# Adafruit_I2S_Audio_UDA1334_Bonnet.net
KiCad netlist of a schematic drawn in EAGLE
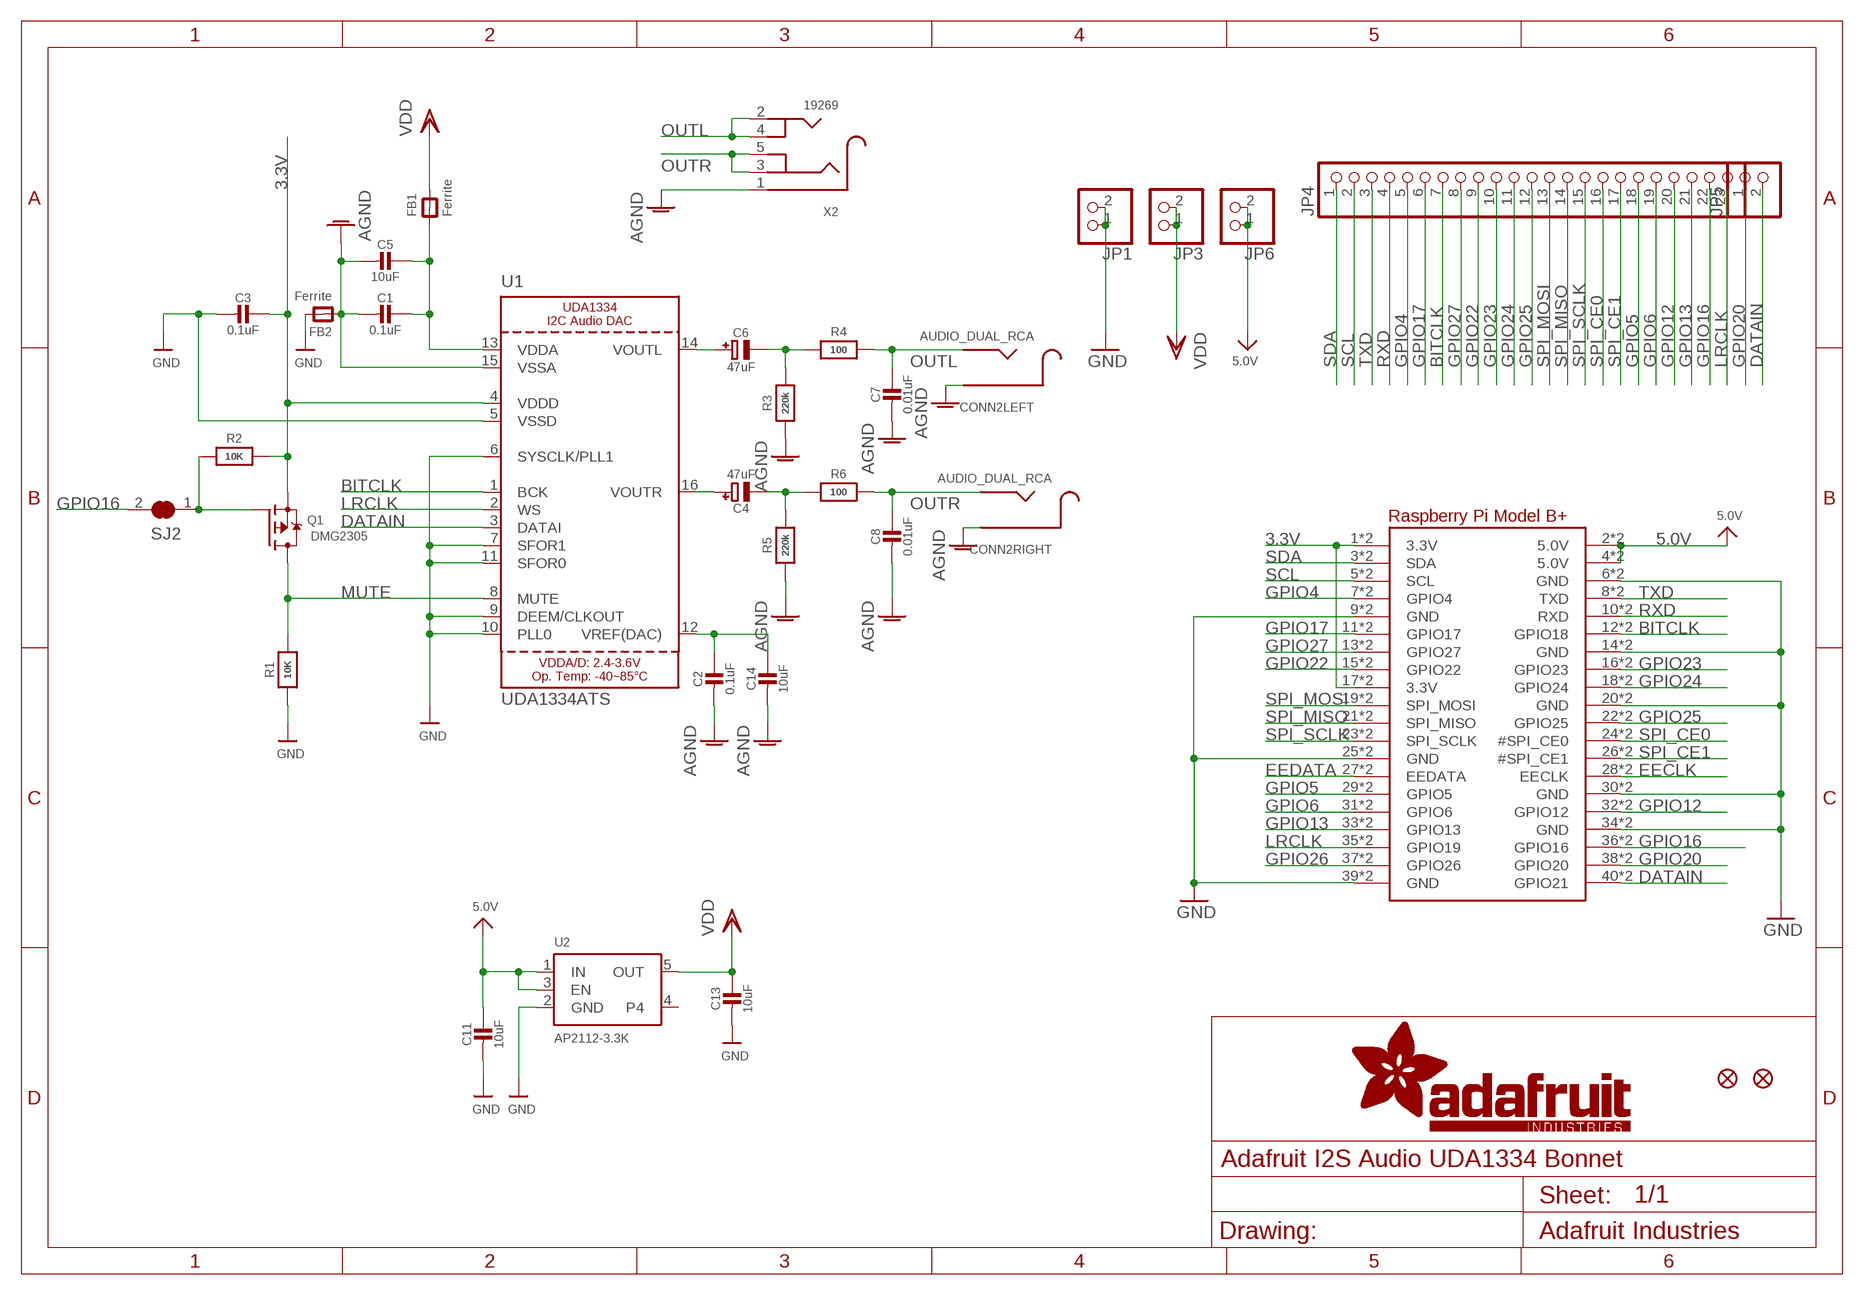
[diagram p0: schematic, sheet 1]

(export (version "E")
  (design (tool "Eeschema 10.0.6"))
  (components
    (comp (ref "C1")
      (value "0.1uF")
      (footprint "eagle-import:0603-NO")
      (libsource (lib "eagle-import") (part "CAP_CERAMIC0603_NO"))
    )
    (comp (ref "C2")
      (value "0.1uF")
      (footprint "eagle-import:0603-NO")
      (libsource (lib "eagle-import") (part "CAP_CERAMIC0603_NO"))
    )
    (comp (ref "C3")
      (value "0.1uF")
      (footprint "eagle-import:0603-NO")
      (libsource (lib "eagle-import") (part "CAP_CERAMIC0603_NO"))
    )
    (comp (ref "C4")
      (value "47uF")
      (footprint "eagle-import:PANASONIC_C")
      (libsource (lib "eagle-import") (part "CAP_ELECTROLYTICPANASONIC_C"))
    )
    (comp (ref "C5")
      (value "10uF")
      (footprint "eagle-import:0805-NO")
      (libsource (lib "eagle-import") (part "CAP_CERAMIC0805-NOOUTLINE"))
    )
    (comp (ref "C6")
      (value "47uF")
      (footprint "eagle-import:PANASONIC_C")
      (libsource (lib "eagle-import") (part "CAP_ELECTROLYTICPANASONIC_C"))
    )
    (comp (ref "C7")
      (value "0.01uF")
      (footprint "eagle-import:0603-NO")
      (libsource (lib "eagle-import") (part "CAP_CERAMIC0603_NO"))
    )
    (comp (ref "C8")
      (value "0.01uF")
      (footprint "eagle-import:0603-NO")
      (libsource (lib "eagle-import") (part "CAP_CERAMIC0603_NO"))
    )
    (comp (ref "C11")
      (value "10uF")
      (footprint "eagle-import:0805-NO")
      (libsource (lib "eagle-import") (part "CAP_CERAMIC0805-NOOUTLINE"))
    )
    (comp (ref "C13")
      (value "10uF")
      (footprint "eagle-import:0805-NO")
      (libsource (lib "eagle-import") (part "CAP_CERAMIC0805-NOOUTLINE"))
    )
    (comp (ref "C14")
      (value "10uF")
      (footprint "eagle-import:0805-NO")
      (libsource (lib "eagle-import") (part "CAP_CERAMIC0805-NOOUTLINE"))
    )
    (comp (ref "CONN2")
      (value "AUDIO_DUAL_RCA")
      (footprint "eagle-import:RCA_DUAL_JACK")
      (libsource (lib "eagle-import") (part "AUDIO_DUAL_RCA"))
    )
    (comp (ref "FB1")
      (value "Ferrite")
      (footprint "eagle-import:0805")
      (libsource (lib "eagle-import") (part "FERRITE0805"))
    )
    (comp (ref "FB2")
      (value "Ferrite")
      (footprint "eagle-import:0805")
      (libsource (lib "eagle-import") (part "FERRITE0805"))
    )
    (comp (ref "FID1")
      (value "FIDUCIAL_1MM")
      (footprint "eagle-import:FIDUCIAL_1MM")
      (libsource (lib "eagle-import") (part "FIDUCIAL_1MM"))
    )
    (comp (ref "FID2")
      (value "FIDUCIAL_1MM")
      (footprint "eagle-import:FIDUCIAL_1MM")
      (libsource (lib "eagle-import") (part "FIDUCIAL_1MM"))
    )
    (comp (ref "JP1")
      (value "HEADER-1X2ROUND")
      (footprint "eagle-import:1X02_ROUND")
      (libsource (lib "eagle-import") (part "HEADER-1X2ROUND"))
    )
    (comp (ref "JP3")
      (value "HEADER-1X2ROUND")
      (footprint "eagle-import:1X02_ROUND")
      (libsource (lib "eagle-import") (part "HEADER-1X2ROUND"))
    )
    (comp (ref "JP4")
      (value "HEADER-1X23")
      (footprint "eagle-import:1X23_ROUND_70MIL")
      (libsource (lib "eagle-import") (part "HEADER-1X23"))
    )
    (comp (ref "JP5")
      (value "HEADER-1X2ROUND")
      (footprint "eagle-import:1X02_ROUND")
      (libsource (lib "eagle-import") (part "HEADER-1X2ROUND"))
    )
    (comp (ref "JP6")
      (value "HEADER-1X2ROUND")
      (footprint "eagle-import:1X02_ROUND")
      (libsource (lib "eagle-import") (part "HEADER-1X2ROUND"))
    )
    (comp (ref "Q1")
      (value "DMG2305")
      (footprint "eagle-import:SOT23-WIDE")
      (libsource (lib "eagle-import") (part "MOSFET-PWIDE"))
    )
    (comp (ref "R1")
      (value "10K")
      (footprint "eagle-import:0603-NO")
      (libsource (lib "eagle-import") (part "RESISTOR_0603_NOOUT"))
    )
    (comp (ref "R2")
      (value "10K")
      (footprint "eagle-import:0603-NO")
      (libsource (lib "eagle-import") (part "RESISTOR_0603_NOOUT"))
    )
    (comp (ref "R3")
      (value "220k")
      (footprint "eagle-import:0603-NO")
      (libsource (lib "eagle-import") (part "RESISTOR_0603_NOOUT"))
    )
    (comp (ref "R4")
      (value "100")
      (footprint "eagle-import:0603-NO")
      (libsource (lib "eagle-import") (part "RESISTOR_0603_NOOUT"))
    )
    (comp (ref "R5")
      (value "220k")
      (footprint "eagle-import:0603-NO")
      (libsource (lib "eagle-import") (part "RESISTOR_0603_NOOUT"))
    )
    (comp (ref "R6")
      (value "100")
      (footprint "eagle-import:0603-NO")
      (libsource (lib "eagle-import") (part "RESISTOR_0603_NOOUT"))
    )
    (comp (ref "RPI1")
      (value "RASPBERRYPI_BPLUS_BONNET_THMSMT")
      (footprint "eagle-import:PI_BONNET_THMSMT")
      (libsource (lib "eagle-import") (part "RASPBERRYPI_BPLUS_BONNET_THMSMT"))
    )
    (comp (ref "SJ2")
      (value "SOLDERJUMPER_CLOSED")
      (footprint "eagle-import:SOLDERJUMPER_CLOSEDWIRE")
      (libsource (lib "eagle-import") (part "SOLDERJUMPER_CLOSED"))
    )
    (comp (ref "U1")
      (value "UDA1334ATS")
      (footprint "eagle-import:SSOP16_4.4MM")
      (libsource (lib "eagle-import") (part "AUDIO_I2S_UDA1334{dblquote}{dblquote}"))
    )
    (comp (ref "U2")
      (value "AP2112-3.3K")
      (footprint "eagle-import:SOT23-5")
      (libsource (lib "eagle-import") (part "VREG_SOT23-5"))
    )
    (comp (ref "X2")
      (value "19269")
      (footprint "eagle-import:4UCONN_19269")
      (libsource (lib "eagle-import") (part "AUDIO_3.5MMJACK"))
    )
  )
  (nets
    (net (code "1") (name "/3.3V") (class "Default")
      (node (ref "C3") (pin "1") (pinfunction "1_1") (pintype "passive"))
      (node (ref "Q1") (pin "2") (pinfunction "S_2") (pintype "passive"))
      (node (ref "R2") (pin "2") (pinfunction "2_2") (pintype "passive"))
      (node (ref "RPI1") (pin "1") (pinfunction "3.3V_1") (pintype "power_in"))
      (node (ref "RPI1") (pin "17") (pinfunction "3.3V_17") (pintype "power_in"))
      (node (ref "RPI1") (pin "S1") (pinfunction "3.3V_S1") (pintype "power_in"))
      (node (ref "RPI1") (pin "S17") (pinfunction "3.3V_S17") (pintype "power_in"))
      (node (ref "U1") (pin "4") (pinfunction "VDDD_4") (pintype "power_in"))
    )
    (net (code "2") (name "/BITCLK") (class "Default")
      (node (ref "JP4") (pin "7") (pinfunction "7_7") (pintype "passive"))
      (node (ref "RPI1") (pin "12") (pinfunction "GPIO18_12") (pintype "bidirectional"))
      (node (ref "RPI1") (pin "S12") (pinfunction "GPIO18_S12") (pintype "bidirectional"))
      (node (ref "U1") (pin "1") (pinfunction "BCK_1") (pintype "input"))
    )
    (net (code "3") (name "/DATAIN") (class "Default")
      (node (ref "JP5") (pin "2") (pinfunction "2_2") (pintype "passive"))
      (node (ref "RPI1") (pin "40") (pinfunction "GPIO21_40") (pintype "bidirectional"))
      (node (ref "RPI1") (pin "S40") (pinfunction "GPIO21_S40") (pintype "bidirectional"))
      (node (ref "U1") (pin "3") (pinfunction "DATAI_3") (pintype "input"))
    )
    (net (code "4") (name "/EECLK") (class "Default")
      (node (ref "RPI1") (pin "28") (pinfunction "EECLK_28") (pintype "bidirectional"))
      (node (ref "RPI1") (pin "S28") (pinfunction "EECLK_S28") (pintype "bidirectional"))
    )
    (net (code "5") (name "/EEDATA") (class "Default")
      (node (ref "RPI1") (pin "27") (pinfunction "EEDATA_27") (pintype "bidirectional"))
      (node (ref "RPI1") (pin "S27") (pinfunction "EEDATA_S27") (pintype "bidirectional"))
    )
    (net (code "6") (name "/GPIO4") (class "Default")
      (node (ref "JP4") (pin "5") (pinfunction "5_5") (pintype "passive"))
      (node (ref "RPI1") (pin "7") (pinfunction "GPIO4_7") (pintype "bidirectional"))
      (node (ref "RPI1") (pin "S7") (pinfunction "GPIO4_S7") (pintype "bidirectional"))
    )
    (net (code "7") (name "/GPIO5") (class "Default")
      (node (ref "JP4") (pin "18") (pinfunction "18_18") (pintype "passive"))
      (node (ref "RPI1") (pin "29") (pinfunction "GPIO5_29") (pintype "bidirectional"))
      (node (ref "RPI1") (pin "S29") (pinfunction "GPIO5_S29") (pintype "bidirectional"))
    )
    (net (code "8") (name "/GPIO6") (class "Default")
      (node (ref "JP4") (pin "19") (pinfunction "19_19") (pintype "passive"))
      (node (ref "RPI1") (pin "31") (pinfunction "GPIO6_31") (pintype "bidirectional"))
      (node (ref "RPI1") (pin "S31") (pinfunction "GPIO6_S31") (pintype "bidirectional"))
    )
    (net (code "9") (name "/GPIO12") (class "Default")
      (node (ref "JP4") (pin "20") (pinfunction "20_20") (pintype "passive"))
      (node (ref "RPI1") (pin "32") (pinfunction "GPIO12_32") (pintype "bidirectional"))
      (node (ref "RPI1") (pin "S32") (pinfunction "GPIO12_S32") (pintype "bidirectional"))
    )
    (net (code "10") (name "/GPIO13") (class "Default")
      (node (ref "JP4") (pin "21") (pinfunction "21_21") (pintype "passive"))
      (node (ref "RPI1") (pin "33") (pinfunction "GPIO13_33") (pintype "bidirectional"))
      (node (ref "RPI1") (pin "S33") (pinfunction "GPIO13_S33") (pintype "bidirectional"))
    )
    (net (code "11") (name "/GPIO16") (class "Default")
      (node (ref "JP4") (pin "22") (pinfunction "22_22") (pintype "passive"))
      (node (ref "RPI1") (pin "36") (pinfunction "GPIO16_36") (pintype "bidirectional"))
      (node (ref "RPI1") (pin "S36") (pinfunction "GPIO16_S36") (pintype "bidirectional"))
      (node (ref "SJ2") (pin "2") (pinfunction "2_2") (pintype "passive"))
    )
    (net (code "12") (name "/GPIO17") (class "Default")
      (node (ref "JP4") (pin "6") (pinfunction "6_6") (pintype "passive"))
      (node (ref "RPI1") (pin "11") (pinfunction "GPIO17_11") (pintype "bidirectional"))
      (node (ref "RPI1") (pin "S11") (pinfunction "GPIO17_S11") (pintype "bidirectional"))
    )
    (net (code "13") (name "/GPIO20") (class "Default")
      (node (ref "JP5") (pin "1") (pinfunction "1_1") (pintype "passive"))
      (node (ref "RPI1") (pin "38") (pinfunction "GPIO20_38") (pintype "bidirectional"))
      (node (ref "RPI1") (pin "S38") (pinfunction "GPIO20_S38") (pintype "bidirectional"))
    )
    (net (code "14") (name "/GPIO22") (class "Default")
      (node (ref "JP4") (pin "9") (pinfunction "9_9") (pintype "passive"))
      (node (ref "RPI1") (pin "15") (pinfunction "GPIO22_15") (pintype "bidirectional"))
      (node (ref "RPI1") (pin "S15") (pinfunction "GPIO22_S15") (pintype "bidirectional"))
    )
    (net (code "15") (name "/GPIO23") (class "Default")
      (node (ref "JP4") (pin "10") (pinfunction "10_10") (pintype "passive"))
      (node (ref "RPI1") (pin "16") (pinfunction "GPIO23_16") (pintype "bidirectional"))
      (node (ref "RPI1") (pin "S16") (pinfunction "GPIO23_S16") (pintype "bidirectional"))
    )
    (net (code "16") (name "/GPIO24") (class "Default")
      (node (ref "JP4") (pin "11") (pinfunction "11_11") (pintype "passive"))
      (node (ref "RPI1") (pin "18") (pinfunction "GPIO24_18") (pintype "bidirectional"))
      (node (ref "RPI1") (pin "S18") (pinfunction "GPIO24_S18") (pintype "bidirectional"))
    )
    (net (code "17") (name "/GPIO25") (class "Default")
      (node (ref "JP4") (pin "12") (pinfunction "12_12") (pintype "passive"))
      (node (ref "RPI1") (pin "22") (pinfunction "GPIO25_22") (pintype "bidirectional"))
      (node (ref "RPI1") (pin "S22") (pinfunction "GPIO25_S22") (pintype "bidirectional"))
    )
    (net (code "18") (name "/GPIO26") (class "Default")
      (node (ref "RPI1") (pin "37") (pinfunction "GPIO26_37") (pintype "bidirectional"))
      (node (ref "RPI1") (pin "S37") (pinfunction "GPIO26_S37") (pintype "bidirectional"))
    )
    (net (code "19") (name "/GPIO27") (class "Default")
      (node (ref "JP4") (pin "8") (pinfunction "8_8") (pintype "passive"))
      (node (ref "RPI1") (pin "13") (pinfunction "GPIO27_13") (pintype "bidirectional"))
      (node (ref "RPI1") (pin "S13") (pinfunction "GPIO27_S13") (pintype "bidirectional"))
    )
    (net (code "20") (name "/LRCLK") (class "Default")
      (node (ref "JP4") (pin "23") (pinfunction "23_23") (pintype "passive"))
      (node (ref "RPI1") (pin "35") (pinfunction "GPIO19_35") (pintype "bidirectional"))
      (node (ref "RPI1") (pin "S35") (pinfunction "GPIO19_S35") (pintype "bidirectional"))
      (node (ref "U1") (pin "2") (pinfunction "WS_2") (pintype "input"))
    )
    (net (code "21") (name "/MUTE") (class "Default")
      (node (ref "Q1") (pin "3") (pinfunction "D_3") (pintype "passive"))
      (node (ref "R1") (pin "2") (pinfunction "2_2") (pintype "passive"))
      (node (ref "U1") (pin "8") (pinfunction "MUTE_8") (pintype "input"))
    )
    (net (code "22") (name "/OUTL") (class "Default")
      (node (ref "C7") (pin "1") (pinfunction "1_1") (pintype "passive"))
      (node (ref "CONN2") (pin "L_SIG") (pinfunction "TIP_L_SIG") (pintype "bidirectional"))
      (node (ref "CONN2") (pin "L_SIG'") (pinfunction "TIP_L_SIG'") (pintype "bidirectional"))
      (node (ref "R4") (pin "2") (pinfunction "2_2") (pintype "passive"))
      (node (ref "X2") (pin "2") (pinfunction "P$5_2") (pintype "bidirectional"))
      (node (ref "X2") (pin "4") (pinfunction "P$4_4") (pintype "bidirectional"))
    )
    (net (code "23") (name "/OUTR") (class "Default")
      (node (ref "C8") (pin "1") (pinfunction "1_1") (pintype "passive"))
      (node (ref "CONN2") (pin "R_SIG") (pinfunction "TIP_R_SIG") (pintype "bidirectional"))
      (node (ref "CONN2") (pin "R_SIG'") (pinfunction "TIP_R_SIG'") (pintype "bidirectional"))
      (node (ref "R6") (pin "2") (pinfunction "2_2") (pintype "passive"))
      (node (ref "X2") (pin "3") (pinfunction "P$2_3") (pintype "bidirectional"))
      (node (ref "X2") (pin "5") (pinfunction "P$3_5") (pintype "bidirectional"))
    )
    (net (code "24") (name "/RXD") (class "Default")
      (node (ref "JP4") (pin "4") (pinfunction "4_4") (pintype "passive"))
      (node (ref "RPI1") (pin "10") (pinfunction "RXD_10") (pintype "bidirectional"))
      (node (ref "RPI1") (pin "S10") (pinfunction "RXD_S10") (pintype "bidirectional"))
    )
    (net (code "25") (name "/SCL") (class "Default")
      (node (ref "JP4") (pin "2") (pinfunction "2_2") (pintype "passive"))
      (node (ref "RPI1") (pin "5") (pinfunction "SCL_5") (pintype "bidirectional"))
      (node (ref "RPI1") (pin "S5") (pinfunction "SCL_S5") (pintype "bidirectional"))
    )
    (net (code "26") (name "/SDA") (class "Default")
      (node (ref "JP4") (pin "1") (pinfunction "1_1") (pintype "passive"))
      (node (ref "RPI1") (pin "3") (pinfunction "SDA_3") (pintype "bidirectional"))
      (node (ref "RPI1") (pin "S3") (pinfunction "SDA_S3") (pintype "bidirectional"))
    )
    (net (code "27") (name "/SPI_CE0") (class "Default")
      (node (ref "JP4") (pin "16") (pinfunction "16_16") (pintype "passive"))
      (node (ref "RPI1") (pin "24") (pinfunction "#SPI_CE0_24") (pintype "bidirectional"))
      (node (ref "RPI1") (pin "S24") (pinfunction "#SPI_CE0_S24") (pintype "bidirectional"))
    )
    (net (code "28") (name "/SPI_CE1") (class "Default")
      (node (ref "JP4") (pin "17") (pinfunction "17_17") (pintype "passive"))
      (node (ref "RPI1") (pin "26") (pinfunction "#SPI_CE1_26") (pintype "bidirectional"))
      (node (ref "RPI1") (pin "S26") (pinfunction "#SPI_CE1_S26") (pintype "bidirectional"))
    )
    (net (code "29") (name "/SPI_MISO") (class "Default")
      (node (ref "JP4") (pin "14") (pinfunction "14_14") (pintype "passive"))
      (node (ref "RPI1") (pin "21") (pinfunction "SPI_MISO_21") (pintype "bidirectional"))
      (node (ref "RPI1") (pin "S21") (pinfunction "SPI_MISO_S21") (pintype "bidirectional"))
    )
    (net (code "30") (name "/SPI_MOSI") (class "Default")
      (node (ref "JP4") (pin "13") (pinfunction "13_13") (pintype "passive"))
      (node (ref "RPI1") (pin "19") (pinfunction "SPI_MOSI_19") (pintype "bidirectional"))
      (node (ref "RPI1") (pin "S19") (pinfunction "SPI_MOSI_S19") (pintype "bidirectional"))
    )
    (net (code "31") (name "/SPI_SCLK") (class "Default")
      (node (ref "JP4") (pin "15") (pinfunction "15_15") (pintype "passive"))
      (node (ref "RPI1") (pin "23") (pinfunction "SPI_SCLK_23") (pintype "bidirectional"))
      (node (ref "RPI1") (pin "S23") (pinfunction "SPI_SCLK_S23") (pintype "bidirectional"))
    )
    (net (code "32") (name "/TXD") (class "Default")
      (node (ref "JP4") (pin "3") (pinfunction "3_3") (pintype "passive"))
      (node (ref "RPI1") (pin "8") (pinfunction "TXD_8") (pintype "bidirectional"))
      (node (ref "RPI1") (pin "S8") (pinfunction "TXD_S8") (pintype "bidirectional"))
    )
    (net (code "33") (name "5.0V") (class "Default")
      (node (ref "C11") (pin "1") (pinfunction "1_1") (pintype "passive"))
      (node (ref "JP6") (pin "1") (pinfunction "1_1") (pintype "passive"))
      (node (ref "JP6") (pin "2") (pinfunction "2_2") (pintype "passive"))
      (node (ref "RPI1") (pin "2") (pinfunction "5.0V_2") (pintype "power_in"))
      (node (ref "RPI1") (pin "4") (pinfunction "5.0V_4") (pintype "power_in"))
      (node (ref "RPI1") (pin "S2") (pinfunction "5.0V_S2") (pintype "power_in"))
      (node (ref "RPI1") (pin "S4") (pinfunction "5.0V_S4") (pintype "power_in"))
      (node (ref "U2") (pin "1") (pinfunction "IN_1") (pintype "power_in"))
      (node (ref "U2") (pin "3") (pinfunction "EN_3") (pintype "input"))
    )
    (net (code "34") (name "AGND") (class "Default")
      (node (ref "C1") (pin "2") (pinfunction "2_2") (pintype "passive"))
      (node (ref "C14") (pin "2") (pinfunction "2_2") (pintype "passive"))
      (node (ref "C2") (pin "2") (pinfunction "2_2") (pintype "passive"))
      (node (ref "C5") (pin "2") (pinfunction "2_2") (pintype "passive"))
      (node (ref "C7") (pin "2") (pinfunction "2_2") (pintype "passive"))
      (node (ref "C8") (pin "2") (pinfunction "2_2") (pintype "passive"))
      (node (ref "CONN2") (pin "L_G") (pinfunction "SLEEVE_L_G") (pintype "bidirectional"))
      (node (ref "CONN2") (pin "L_G'") (pinfunction "SLEEVE_L_G'") (pintype "bidirectional"))
      (node (ref "CONN2") (pin "R_G") (pinfunction "SLEEVE_R_G") (pintype "bidirectional"))
      (node (ref "CONN2") (pin "R_G'") (pinfunction "SLEEVE_R_G'") (pintype "bidirectional"))
      (node (ref "FB2") (pin "1") (pinfunction "P$1_1") (pintype "passive"))
      (node (ref "R3") (pin "1") (pinfunction "1_1") (pintype "passive"))
      (node (ref "R5") (pin "1") (pinfunction "1_1") (pintype "passive"))
      (node (ref "U1") (pin "15") (pinfunction "VSSA_15") (pintype "power_in"))
      (node (ref "X2") (pin "1") (pinfunction "P$1_1") (pintype "bidirectional"))
    )
    (net (code "35") (name "GND") (class "Default")
      (node (ref "C11") (pin "2") (pinfunction "2_2") (pintype "passive"))
      (node (ref "C13") (pin "2") (pinfunction "2_2") (pintype "passive"))
      (node (ref "C3") (pin "2") (pinfunction "2_2") (pintype "passive"))
      (node (ref "FB2") (pin "2") (pinfunction "P$2_2") (pintype "passive"))
      (node (ref "JP1") (pin "1") (pinfunction "1_1") (pintype "passive"))
      (node (ref "JP1") (pin "2") (pinfunction "2_2") (pintype "passive"))
      (node (ref "R1") (pin "1") (pinfunction "1_1") (pintype "passive"))
      (node (ref "RPI1") (pin "14") (pinfunction "GND_14") (pintype "power_in"))
      (node (ref "RPI1") (pin "20") (pinfunction "GND_20") (pintype "power_in"))
      (node (ref "RPI1") (pin "25") (pinfunction "GND_25") (pintype "power_in"))
      (node (ref "RPI1") (pin "30") (pinfunction "GND_30") (pintype "power_in"))
      (node (ref "RPI1") (pin "34") (pinfunction "GND_34") (pintype "power_in"))
      (node (ref "RPI1") (pin "39") (pinfunction "GND_39") (pintype "power_in"))
      (node (ref "RPI1") (pin "6") (pinfunction "GND_6") (pintype "power_in"))
      (node (ref "RPI1") (pin "9") (pinfunction "GND_9") (pintype "power_in"))
      (node (ref "RPI1") (pin "S14") (pinfunction "GND_S14") (pintype "power_in"))
      (node (ref "RPI1") (pin "S20") (pinfunction "GND_S20") (pintype "power_in"))
      (node (ref "RPI1") (pin "S25") (pinfunction "GND_S25") (pintype "power_in"))
      (node (ref "RPI1") (pin "S30") (pinfunction "GND_S30") (pintype "power_in"))
      (node (ref "RPI1") (pin "S34") (pinfunction "GND_S34") (pintype "power_in"))
      (node (ref "RPI1") (pin "S39") (pinfunction "GND_S39") (pintype "power_in"))
      (node (ref "RPI1") (pin "S6") (pinfunction "GND_S6") (pintype "power_in"))
      (node (ref "RPI1") (pin "S9") (pinfunction "GND_S9") (pintype "power_in"))
      (node (ref "U1") (pin "10") (pinfunction "PLL0_10") (pintype "input"))
      (node (ref "U1") (pin "11") (pinfunction "SFOR0_11") (pintype "input"))
      (node (ref "U1") (pin "5") (pinfunction "VSSD_5") (pintype "power_in"))
      (node (ref "U1") (pin "6") (pinfunction "SYSCLK/PLL1_6") (pintype "input"))
      (node (ref "U1") (pin "7") (pinfunction "SFOR1_7") (pintype "input"))
      (node (ref "U1") (pin "9") (pinfunction "DEEM/CLKOUT_9") (pintype "bidirectional"))
      (node (ref "U2") (pin "2") (pinfunction "GND_2") (pintype "power_in"))
    )
    (net (code "36") (name "Net-(C4-Pad-)") (class "Default")
      (node (ref "C4") (pin "-") (pinfunction "-_-") (pintype "passive"))
      (node (ref "R5") (pin "2") (pinfunction "2_2") (pintype "passive"))
      (node (ref "R6") (pin "1") (pinfunction "1_1") (pintype "passive"))
    )
    (net (code "37") (name "Net-(C6-Pad-)") (class "Default")
      (node (ref "C6") (pin "-") (pinfunction "-_-") (pintype "passive"))
      (node (ref "R3") (pin "2") (pinfunction "2_2") (pintype "passive"))
      (node (ref "R4") (pin "1") (pinfunction "1_1") (pintype "passive"))
    )
    (net (code "38") (name "Net-(FB1-P$1)") (class "Default")
      (node (ref "C1") (pin "1") (pinfunction "1_1") (pintype "passive"))
      (node (ref "C5") (pin "1") (pinfunction "1_1") (pintype "passive"))
      (node (ref "FB1") (pin "1") (pinfunction "P$1_1") (pintype "passive"))
      (node (ref "U1") (pin "13") (pinfunction "VDDA_13") (pintype "power_in"))
    )
    (net (code "39") (name "Net-(Q1-G)") (class "Default")
      (node (ref "Q1") (pin "1") (pinfunction "G_1") (pintype "passive"))
      (node (ref "R2") (pin "1") (pinfunction "1_1") (pintype "passive"))
      (node (ref "SJ2") (pin "1") (pinfunction "1_1") (pintype "passive"))
    )
    (net (code "40") (name "Net-(U1-VOUTL)") (class "Default")
      (node (ref "C6") (pin "+") (pinfunction "+_+") (pintype "passive"))
      (node (ref "U1") (pin "14") (pinfunction "VOUTL_14") (pintype "output"))
    )
    (net (code "41") (name "Net-(U1-VOUTR)") (class "Default")
      (node (ref "C4") (pin "+") (pinfunction "+_+") (pintype "passive"))
      (node (ref "U1") (pin "16") (pinfunction "VOUTR_16") (pintype "output"))
    )
    (net (code "42") (name "Net-(U1-VREF(DAC))") (class "Default")
      (node (ref "C14") (pin "1") (pinfunction "1_1") (pintype "passive"))
      (node (ref "C2") (pin "1") (pinfunction "1_1") (pintype "passive"))
      (node (ref "U1") (pin "12") (pinfunction "VREF(DAC)_12") (pintype "output"))
    )
    (net (code "43") (name "VDD") (class "Default")
      (node (ref "C13") (pin "1") (pinfunction "1_1") (pintype "passive"))
      (node (ref "FB1") (pin "2") (pinfunction "P$2_2") (pintype "passive"))
      (node (ref "JP3") (pin "1") (pinfunction "1_1") (pintype "passive"))
      (node (ref "JP3") (pin "2") (pinfunction "2_2") (pintype "passive"))
      (node (ref "U2") (pin "5") (pinfunction "OUT_5") (pintype "power_in"))
    )
    (net (code "44") (name "unconnected-(U2-P4-Pad4)") (class "Default")
      (node (ref "U2") (pin "4") (pinfunction "P4_4") (pintype "bidirectional"))
    )
  )
)
